# Core.net
KiCad netlist of a schematic drawn in Altium Designer
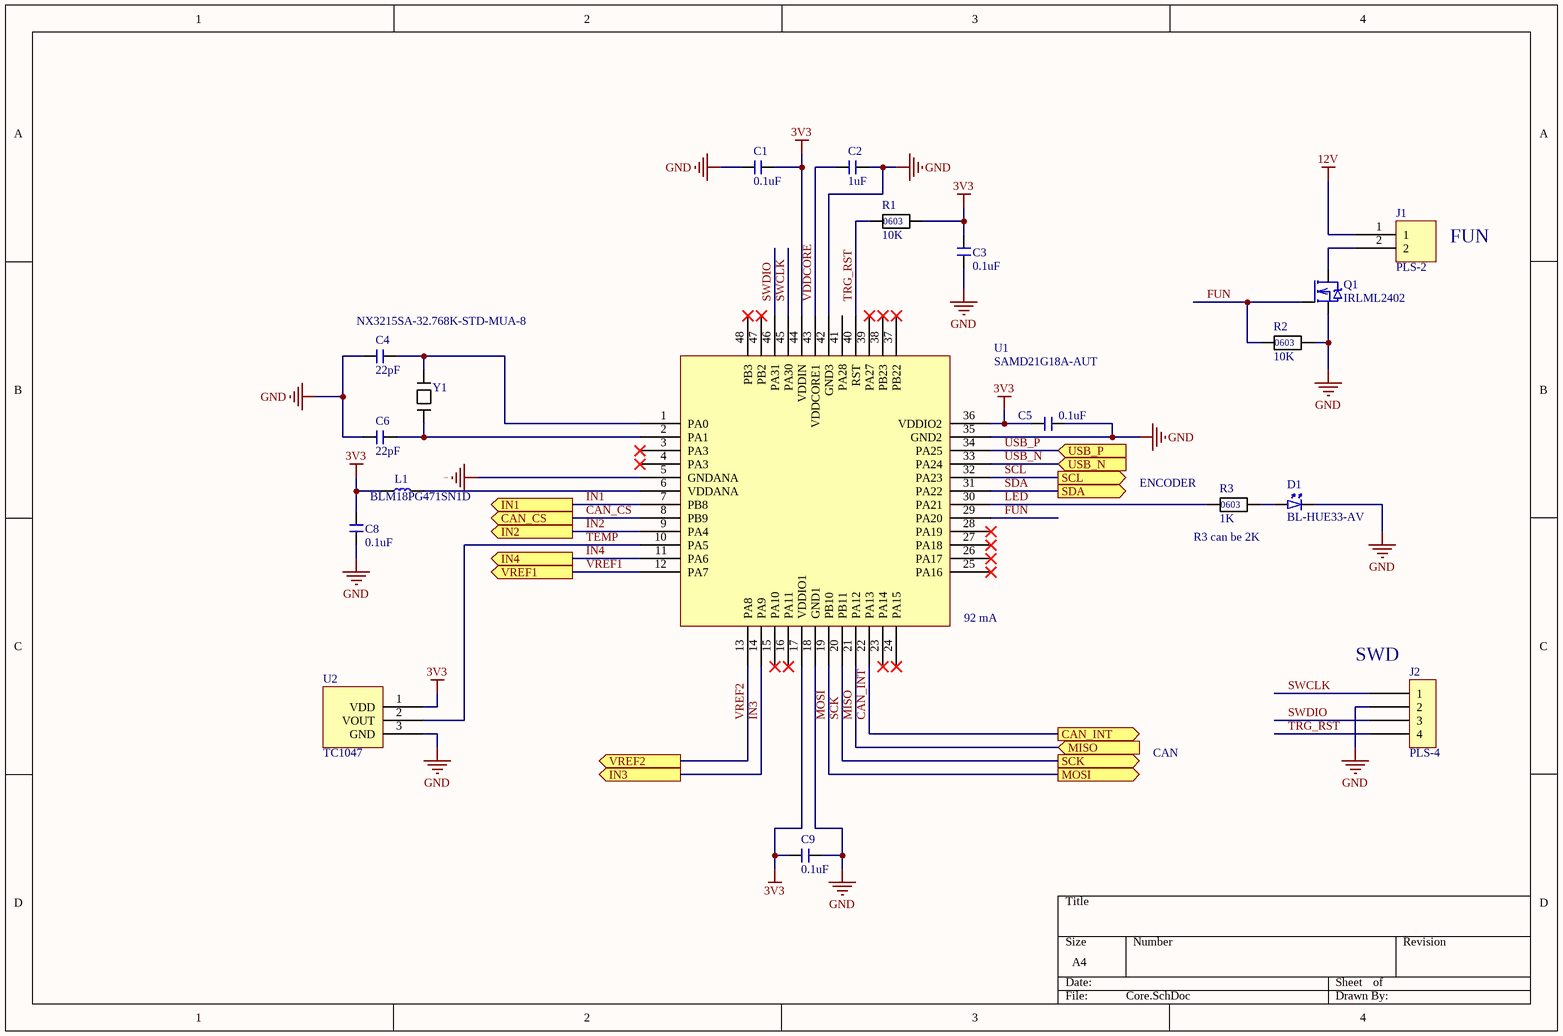
[diagram p0: Core.SchDoc]

(export (version "E")
  (design (tool "Eeschema 10.0.6"))
  (components
    (comp (ref "C1") (value "0.1uF") (footprint "CHIP_C_0603") (libsource (lib "Popular") (part "CHIP_C")))
    (comp (ref "C2") (value "1uF") (footprint "CHIP_C_0603") (libsource (lib "Popular") (part "CHIP_C")))
    (comp (ref "C3") (value "0.1uF") (footprint "CHIP_C_0603") (libsource (lib "Popular") (part "CHIP_C")))
    (comp (ref "C4") (value "22pF") (footprint "CHIP_C_0603") (libsource (lib "Popular") (part "CHIP_C")))
    (comp (ref "C5") (value "0.1uF") (footprint "CHIP_C_0603") (libsource (lib "Popular") (part "CHIP_C")))
    (comp (ref "C6") (value "22pF") (footprint "CHIP_C_0603") (libsource (lib "Popular") (part "CHIP_C")))
    (comp (ref "C8") (value "0.1uF") (footprint "CHIP_C_0603") (libsource (lib "Popular") (part "CHIP_C")))
    (comp (ref "C9") (value "0.1uF") (footprint "CHIP_C_0603") (libsource (lib "Popular") (part "CHIP_C")))
    (comp (ref "D1")
      (value "BL-HUE33-AV")
      (footprint "CHIP_D_0603")
      (description "LED")
      (libsource (lib "Popular") (part "KP-3216"))
    )
    (comp (ref "J1")
      (value "PLS-2")
      (footprint "PLS-2")
      (description "Connector")
      (libsource (lib "Popular") (part "PLS-2"))
    )
    (comp (ref "J2") (value "PLS-4") (footprint "PLS-4") (libsource (lib "Popular") (part "PLS-4")))
    (comp (ref "L1")
      (value "BLM18PG471SN1D")
      (footprint "CHIP_R_0603")
      (libsource (lib "Popular") (part "BLM"))
    )
    (comp (ref "Q1")
      (value "IRLML2402")
      (footprint "SOT23")
      (description "n-chanal MOSFET")
      (libsource (lib "Popular") (part "IRLML2402"))
    )
    (comp (ref "R1") (value "10K") (footprint "CHIP_R_0603") (libsource (lib "Popular") (part "RES_0603")))
    (comp (ref "R2") (value "10K") (footprint "CHIP_R_0603") (libsource (lib "Popular") (part "RES_0603")))
    (comp (ref "R3") (value "1K") (footprint "CHIP_R_0603") (libsource (lib "Popular") (part "RES_0603")))
    (comp (ref "U1")
      (value "SAMD21G18A-AUT")
      (footprint "LQFP48")
      (libsource (lib "STM32") (part "SAMD21G18A-AUT"))
    )
    (comp (ref "U2")
      (value "TC1047")
      (footprint "SOT23")
      (description "Temperature Sensor")
      (libsource (lib "Popular") (part "TC1047"))
    )
    (comp (ref "Y1")
      (value "NX3215SA-32.768K-STD-MUA-8")
      (footprint "NX3215SA")
      (libsource (lib "Popular") (part "Quartz"))
    )
  )
  (nets
    (net (code "1") (name "/CAN_CS") (class "Default")
      (node (ref "U1") (pin "8") (pinfunction "PB9_8") (pintype "passive"))
    )
    (net (code "2") (name "/CAN_INT") (class "Default")
      (node (ref "U1") (pin "22") (pinfunction "PA13_22") (pintype "passive"))
    )
    (net (code "3") (name "/FUN") (class "Default")
      (node (ref "Q1") (pin "1") (pinfunction "G_1") (pintype "passive"))
      (node (ref "R2") (pin "1") (pinfunction "1_1") (pintype "passive"))
      (node (ref "U1") (pin "29") (pinfunction "PA20_29") (pintype "passive"))
    )
    (net (code "4") (name "/IN1") (class "Default")
      (node (ref "U1") (pin "7") (pinfunction "PB8_7") (pintype "passive"))
    )
    (net (code "5") (name "/IN2") (class "Default")
      (node (ref "U1") (pin "9") (pinfunction "PA4_9") (pintype "passive"))
    )
    (net (code "6") (name "/IN3") (class "Default")
      (node (ref "U1") (pin "14") (pinfunction "PA9_14") (pintype "passive"))
    )
    (net (code "7") (name "/IN4") (class "Default")
      (node (ref "U1") (pin "11") (pinfunction "PA6_11") (pintype "passive"))
    )
    (net (code "8") (name "/LED") (class "Default")
      (node (ref "R3") (pin "1") (pinfunction "1_1") (pintype "passive"))
      (node (ref "U1") (pin "30") (pinfunction "PA21_30") (pintype "passive"))
    )
    (net (code "9") (name "/MISO") (class "Default")
      (node (ref "U1") (pin "21") (pinfunction "PA12_21") (pintype "passive"))
    )
    (net (code "10") (name "/MOSI") (class "Default")
      (node (ref "U1") (pin "19") (pinfunction "PB10_19") (pintype "passive"))
    )
    (net (code "11") (name "/SCK") (class "Default")
      (node (ref "U1") (pin "20") (pinfunction "PB11_20") (pintype "passive"))
    )
    (net (code "12") (name "/SCL") (class "Default")
      (node (ref "U1") (pin "32") (pinfunction "PA23_32") (pintype "passive"))
    )
    (net (code "13") (name "/SDA") (class "Default")
      (node (ref "U1") (pin "31") (pinfunction "PA22_31") (pintype "passive"))
    )
    (net (code "14") (name "/SWCLK") (class "Default")
      (node (ref "J2") (pin "1") (pinfunction "1_1") (pintype "passive"))
      (node (ref "U1") (pin "45") (pinfunction "PA30_45") (pintype "passive"))
    )
    (net (code "15") (name "/SWDIO") (class "Default")
      (node (ref "J2") (pin "3") (pinfunction "3_3") (pintype "passive"))
      (node (ref "U1") (pin "46") (pinfunction "PA31_46") (pintype "passive"))
    )
    (net (code "16") (name "/TEMP") (class "Default")
      (node (ref "U1") (pin "10") (pinfunction "PA5_10") (pintype "passive"))
      (node (ref "U2") (pin "2") (pinfunction "VOUT_2") (pintype "passive"))
    )
    (net (code "17") (name "/TRG_RST") (class "Default")
      (node (ref "J2") (pin "4") (pinfunction "4_4") (pintype "passive"))
      (node (ref "R1") (pin "1") (pinfunction "1_1") (pintype "passive"))
      (node (ref "U1") (pin "40") (pinfunction "RST_40") (pintype "passive"))
    )
    (net (code "18") (name "/USB_N") (class "Default")
      (node (ref "U1") (pin "33") (pinfunction "PA24_33") (pintype "passive"))
    )
    (net (code "19") (name "/USB_P") (class "Default")
      (node (ref "U1") (pin "34") (pinfunction "PA25_34") (pintype "passive"))
    )
    (net (code "20") (name "/VDDCORE") (class "Default")
      (node (ref "C2") (pin "1") (pinfunction "1_1") (pintype "passive"))
      (node (ref "U1") (pin "43") (pinfunction "VDDCORE1_43") (pintype "passive"))
    )
    (net (code "21") (name "/VREF1") (class "Default")
      (node (ref "U1") (pin "12") (pinfunction "PA7_12") (pintype "passive"))
    )
    (net (code "22") (name "/VREF2") (class "Default")
      (node (ref "U1") (pin "13") (pinfunction "PA8_13") (pintype "passive"))
    )
    (net (code "23") (name "3V3") (class "Default")
      (node (ref "C1") (pin "2") (pinfunction "2_2") (pintype "passive"))
      (node (ref "C3") (pin "2") (pinfunction "2_2") (pintype "passive"))
      (node (ref "C5") (pin "1") (pinfunction "1_1") (pintype "passive"))
      (node (ref "C8") (pin "2") (pinfunction "2_2") (pintype "passive"))
      (node (ref "C9") (pin "1") (pinfunction "1_1") (pintype "passive"))
      (node (ref "L1") (pin "1") (pinfunction "1_1") (pintype "passive"))
      (node (ref "R1") (pin "2") (pinfunction "2_2") (pintype "passive"))
      (node (ref "U1") (pin "17") (pinfunction "VDDIO1_17") (pintype "passive"))
      (node (ref "U1") (pin "36") (pinfunction "VDDIO2_36") (pintype "passive"))
      (node (ref "U1") (pin "44") (pinfunction "VDDIN_44") (pintype "passive"))
      (node (ref "U2") (pin "1") (pinfunction "VDD_1") (pintype "passive"))
    )
    (net (code "24") (name "12V") (class "Default")
      (node (ref "J1") (pin "1") (pinfunction "1_1") (pintype "passive"))
    )
    (net (code "25") (name "GND") (class "Default")
      (node (ref "C1") (pin "1") (pinfunction "1_1") (pintype "passive"))
      (node (ref "C2") (pin "2") (pinfunction "2_2") (pintype "passive"))
      (node (ref "C3") (pin "1") (pinfunction "1_1") (pintype "passive"))
      (node (ref "C4") (pin "1") (pinfunction "1_1") (pintype "passive"))
      (node (ref "C5") (pin "2") (pinfunction "2_2") (pintype "passive"))
      (node (ref "C6") (pin "1") (pinfunction "1_1") (pintype "passive"))
      (node (ref "C8") (pin "1") (pinfunction "1_1") (pintype "passive"))
      (node (ref "C9") (pin "2") (pinfunction "2_2") (pintype "passive"))
      (node (ref "D1") (pin "2") (pinfunction "C_2") (pintype "passive"))
      (node (ref "J2") (pin "2") (pinfunction "2_2") (pintype "passive"))
      (node (ref "Q1") (pin "2") (pinfunction "S_2") (pintype "passive"))
      (node (ref "R2") (pin "2") (pinfunction "2_2") (pintype "passive"))
      (node (ref "U1") (pin "18") (pinfunction "GND1_18") (pintype "passive"))
      (node (ref "U1") (pin "35") (pinfunction "GND2_35") (pintype "passive"))
      (node (ref "U1") (pin "42") (pinfunction "GND3_42") (pintype "passive"))
      (node (ref "U1") (pin "5") (pinfunction "GNDANA_5") (pintype "passive"))
      (node (ref "U2") (pin "3") (pinfunction "GND_3") (pintype "passive"))
    )
    (net (code "26") (name "Net-(D1-A)") (class "Default")
      (node (ref "D1") (pin "1") (pinfunction "A_1") (pintype "passive"))
      (node (ref "R3") (pin "2") (pinfunction "2_2") (pintype "passive"))
    )
    (net (code "27") (name "Net-(Q1-D)") (class "Default")
      (node (ref "J1") (pin "2") (pinfunction "2_2") (pintype "passive"))
      (node (ref "Q1") (pin "3") (pinfunction "D_3") (pintype "passive"))
    )
    (net (code "28") (name "Net-(U1-PA0)") (class "Default")
      (node (ref "C4") (pin "2") (pinfunction "2_2") (pintype "passive"))
      (node (ref "U1") (pin "1") (pinfunction "PA0_1") (pintype "passive"))
      (node (ref "Y1") (pin "2") (pinfunction "2_2") (pintype "passive"))
    )
    (net (code "29") (name "Net-(U1-PA1)") (class "Default")
      (node (ref "C6") (pin "2") (pinfunction "2_2") (pintype "passive"))
      (node (ref "U1") (pin "2") (pinfunction "PA1_2") (pintype "passive"))
      (node (ref "Y1") (pin "1") (pinfunction "1_1") (pintype "passive"))
    )
    (net (code "30") (name "Net-(U1-VDDANA)") (class "Default")
      (node (ref "L1") (pin "2") (pinfunction "2_2") (pintype "passive"))
      (node (ref "U1") (pin "6") (pinfunction "VDDANA_6") (pintype "passive"))
    )
    (net (code "31") (name "unconnected-(U1-PA3-Pad3)") (class "Default")
      (node (ref "U1") (pin "3") (pinfunction "PA3_3") (pintype "passive+no_connect"))
    )
    (net (code "32") (name "unconnected-(U1-PA3-Pad4)") (class "Default")
      (node (ref "U1") (pin "4") (pinfunction "PA3_4") (pintype "passive+no_connect"))
    )
    (net (code "33") (name "unconnected-(U1-PA10-Pad15)") (class "Default")
      (node (ref "U1") (pin "15") (pinfunction "PA10_15") (pintype "passive+no_connect"))
    )
    (net (code "34") (name "unconnected-(U1-PA11-Pad16)") (class "Default")
      (node (ref "U1") (pin "16") (pinfunction "PA11_16") (pintype "passive+no_connect"))
    )
    (net (code "35") (name "unconnected-(U1-PA14-Pad23)") (class "Default")
      (node (ref "U1") (pin "23") (pinfunction "PA14_23") (pintype "passive+no_connect"))
    )
    (net (code "36") (name "unconnected-(U1-PA15-Pad24)") (class "Default")
      (node (ref "U1") (pin "24") (pinfunction "PA15_24") (pintype "passive+no_connect"))
    )
    (net (code "37") (name "unconnected-(U1-PA16-Pad25)") (class "Default")
      (node (ref "U1") (pin "25") (pinfunction "PA16_25") (pintype "passive+no_connect"))
    )
    (net (code "38") (name "unconnected-(U1-PA17-Pad26)") (class "Default")
      (node (ref "U1") (pin "26") (pinfunction "PA17_26") (pintype "passive+no_connect"))
    )
    (net (code "39") (name "unconnected-(U1-PA18-Pad27)") (class "Default")
      (node (ref "U1") (pin "27") (pinfunction "PA18_27") (pintype "passive+no_connect"))
    )
    (net (code "40") (name "unconnected-(U1-PA19-Pad28)") (class "Default")
      (node (ref "U1") (pin "28") (pinfunction "PA19_28") (pintype "passive+no_connect"))
    )
    (net (code "41") (name "unconnected-(U1-PA27-Pad39)") (class "Default")
      (node (ref "U1") (pin "39") (pinfunction "PA27_39") (pintype "passive+no_connect"))
    )
    (net (code "42") (name "unconnected-(U1-PA28-Pad41)") (class "Default")
      (node (ref "U1") (pin "41") (pinfunction "PA28_41") (pintype "passive"))
    )
    (net (code "43") (name "unconnected-(U1-PB2-Pad47)") (class "Default")
      (node (ref "U1") (pin "47") (pinfunction "PB2_47") (pintype "passive+no_connect"))
    )
    (net (code "44") (name "unconnected-(U1-PB3-Pad48)") (class "Default")
      (node (ref "U1") (pin "48") (pinfunction "PB3_48") (pintype "passive+no_connect"))
    )
    (net (code "45") (name "unconnected-(U1-PB22-Pad37)") (class "Default")
      (node (ref "U1") (pin "37") (pinfunction "PB22_37") (pintype "passive+no_connect"))
    )
    (net (code "46") (name "unconnected-(U1-PB23-Pad38)") (class "Default")
      (node (ref "U1") (pin "38") (pinfunction "PB23_38") (pintype "passive+no_connect"))
    )
  )
)
